# e3_tp2_ej4.net
KiCad netlist of a schematic drawn in Altium Designer
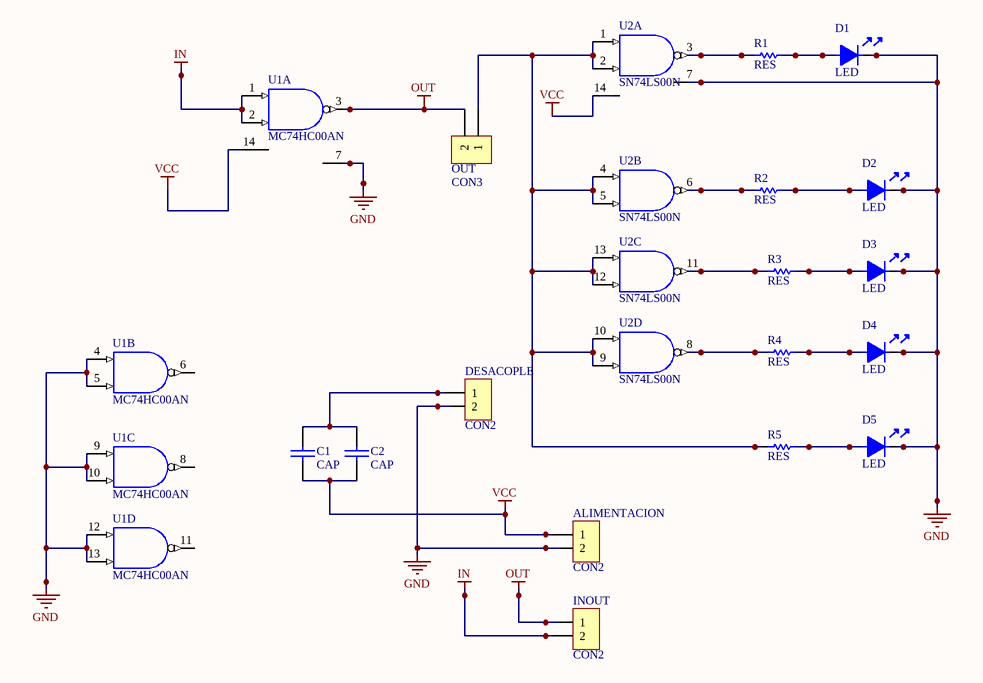
[diagram p0: e3_tp2_ej4.SchDoc]

(export (version "E")
  (design (tool "Eeschema 10.0.6"))
  (components
    (comp (ref "ALIMENTACION") (value "CON2") (footprint "SIP2") (libsource (lib "LIBEBAL") (part "CON2")))
    (comp (ref "C1") (value "CAP") (footprint "CAP200") (libsource (lib "LIBEBAL") (part "CAP")))
    (comp (ref "C2") (value "CAP") (footprint "CAP200") (libsource (lib "LIBEBAL") (part "CAP")))
    (comp (ref "D1") (value "LED") (footprint "LED3") (libsource (lib "LIBEBAL") (part "LED")))
    (comp (ref "D2") (value "LED") (footprint "LED3") (libsource (lib "LIBEBAL") (part "LED")))
    (comp (ref "D3") (value "LED") (footprint "LED3") (libsource (lib "LIBEBAL") (part "LED")))
    (comp (ref "D4") (value "LED") (footprint "LED3") (libsource (lib "LIBEBAL") (part "LED")))
    (comp (ref "D5") (value "LED") (footprint "LED3") (libsource (lib "LIBEBAL") (part "LED")))
    (comp (ref "DESACOPLE") (value "CON2") (footprint "SIP2") (libsource (lib "LIBEBAL") (part "CON2")))
    (comp (ref "INOUT") (value "CON2") (footprint "SIP2") (libsource (lib "LIBEBAL") (part "CON2")))
    (comp (ref "OUT") (value "CON3") (footprint "SIP2") (libsource (lib "") (part "CON2_1")))
    (comp (ref "R1") (value "RES") (footprint "RES300") (libsource (lib "LIBEBAL") (part "RES")))
    (comp (ref "R2") (value "RES") (footprint "RES300") (libsource (lib "LIBEBAL") (part "RES")))
    (comp (ref "R3") (value "RES") (footprint "RES300") (libsource (lib "LIBEBAL") (part "RES")))
    (comp (ref "R4") (value "RES") (footprint "RES300") (libsource (lib "LIBEBAL") (part "RES")))
    (comp (ref "R5") (value "RES") (footprint "RES300") (libsource (lib "LIBEBAL") (part "RES")))
    (comp (ref "U1")
      (value "MC74HC00AN")
      (footprint "646-06")
      (description "Quad 2-Input NAND Gate")
      (fields (field (name "PUBLISHER") "Altium Limited"))
      (libsource (lib "ON Semi Logic Gate") (part "MC74HC00AN"))
    )
    (comp (ref "U2")
      (value "SN74LS00N")
      (footprint "646-06")
      (description "Quad 2-Input NAND Gate")
      (fields (field (name "PUBLISHER") "Altium Limited"))
      (libsource (lib "ON Semi Logic Gate") (part "SN74LS00N"))
    )
  )
  (nets
    (net (code "1") (name "GND") (class "Default")
      (node (ref "ALIMENTACION") (pin "2") (pinfunction "2_2") (pintype "passive"))
      (node (ref "D1") (pin "2") (pinfunction "2_2") (pintype "passive"))
      (node (ref "D2") (pin "2") (pinfunction "2_2") (pintype "passive"))
      (node (ref "D3") (pin "2") (pinfunction "2_2") (pintype "passive"))
      (node (ref "D4") (pin "2") (pinfunction "2_2") (pintype "passive"))
      (node (ref "D5") (pin "2") (pinfunction "2_2") (pintype "passive"))
      (node (ref "DESACOPLE") (pin "2") (pinfunction "2_2") (pintype "passive"))
      (node (ref "U1") (pin "10") (pinfunction "B_10") (pintype "input"))
      (node (ref "U1") (pin "12") (pinfunction "A_12") (pintype "input"))
      (node (ref "U1") (pin "13") (pinfunction "B_13") (pintype "input"))
      (node (ref "U1") (pin "4") (pinfunction "A_4") (pintype "input"))
      (node (ref "U1") (pin "5") (pinfunction "B_5") (pintype "input"))
      (node (ref "U1") (pin "7") (pinfunction "GND_7") (pintype "power_in"))
      (node (ref "U1") (pin "9") (pinfunction "A_9") (pintype "input"))
      (node (ref "U2") (pin "7") (pinfunction "GND_7") (pintype "power_in"))
    )
    (net (code "2") (name "IN") (class "Default")
      (node (ref "INOUT") (pin "2") (pinfunction "2_2") (pintype "passive"))
      (node (ref "U1") (pin "1") (pinfunction "A_1") (pintype "input"))
      (node (ref "U1") (pin "2") (pinfunction "B_2") (pintype "input"))
    )
    (net (code "3") (name "Net-(C1-Pad1)") (class "Default")
      (node (ref "C1") (pin "1") (pinfunction "1_1") (pintype "passive"))
      (node (ref "C2") (pin "1") (pinfunction "1_1") (pintype "passive"))
      (node (ref "DESACOPLE") (pin "1") (pinfunction "1_1") (pintype "passive"))
    )
    (net (code "4") (name "Net-(D1-Pad1)") (class "Default")
      (node (ref "D1") (pin "1") (pinfunction "1_1") (pintype "passive"))
      (node (ref "R1") (pin "2") (pinfunction "2_2") (pintype "passive"))
    )
    (net (code "5") (name "Net-(D2-Pad1)") (class "Default")
      (node (ref "D2") (pin "1") (pinfunction "1_1") (pintype "passive"))
      (node (ref "R2") (pin "2") (pinfunction "2_2") (pintype "passive"))
    )
    (net (code "6") (name "Net-(D3-Pad1)") (class "Default")
      (node (ref "D3") (pin "1") (pinfunction "1_1") (pintype "passive"))
      (node (ref "R3") (pin "2") (pinfunction "2_2") (pintype "passive"))
    )
    (net (code "7") (name "Net-(D4-Pad1)") (class "Default")
      (node (ref "D4") (pin "1") (pinfunction "1_1") (pintype "passive"))
      (node (ref "R4") (pin "2") (pinfunction "2_2") (pintype "passive"))
    )
    (net (code "8") (name "Net-(D5-Pad1)") (class "Default")
      (node (ref "D5") (pin "1") (pinfunction "1_1") (pintype "passive"))
      (node (ref "R5") (pin "2") (pinfunction "2_2") (pintype "passive"))
    )
    (net (code "9") (name "Net-(U2A-A)") (class "Default")
      (node (ref "OUT") (pin "1") (pinfunction "1_1") (pintype "passive"))
      (node (ref "R5") (pin "1") (pinfunction "1_1") (pintype "passive"))
      (node (ref "U2") (pin "1") (pinfunction "A_1") (pintype "input"))
      (node (ref "U2") (pin "10") (pinfunction "A_10") (pintype "input"))
      (node (ref "U2") (pin "12") (pinfunction "B_12") (pintype "input"))
      (node (ref "U2") (pin "13") (pinfunction "A_13") (pintype "input"))
      (node (ref "U2") (pin "2") (pinfunction "B_2") (pintype "input"))
      (node (ref "U2") (pin "4") (pinfunction "A_4") (pintype "input"))
      (node (ref "U2") (pin "5") (pinfunction "B_5") (pintype "input"))
      (node (ref "U2") (pin "9") (pinfunction "B_9") (pintype "input"))
    )
    (net (code "10") (name "Net-(U2A-~{O})") (class "Default")
      (node (ref "R1") (pin "1") (pinfunction "1_1") (pintype "passive"))
      (node (ref "U2") (pin "3") (pinfunction "~{O}_3") (pintype "output"))
    )
    (net (code "11") (name "Net-(U2B-~{O})") (class "Default")
      (node (ref "R2") (pin "1") (pinfunction "1_1") (pintype "passive"))
      (node (ref "U2") (pin "6") (pinfunction "~{O}_6") (pintype "output"))
    )
    (net (code "12") (name "Net-(U2C-~{O})") (class "Default")
      (node (ref "R3") (pin "1") (pinfunction "1_1") (pintype "passive"))
      (node (ref "U2") (pin "11") (pinfunction "~{O}_11") (pintype "output"))
    )
    (net (code "13") (name "Net-(U2D-~{O})") (class "Default")
      (node (ref "R4") (pin "1") (pinfunction "1_1") (pintype "passive"))
      (node (ref "U2") (pin "8") (pinfunction "~{O}_8") (pintype "output"))
    )
    (net (code "14") (name "OUT") (class "Default")
      (node (ref "INOUT") (pin "1") (pinfunction "1_1") (pintype "passive"))
      (node (ref "OUT") (pin "2") (pinfunction "2_2") (pintype "passive"))
      (node (ref "U1") (pin "3") (pinfunction "~{Y}_3") (pintype "output"))
    )
    (net (code "15") (name "VCC") (class "Default")
      (node (ref "ALIMENTACION") (pin "1") (pinfunction "1_1") (pintype "passive"))
      (node (ref "C1") (pin "2") (pinfunction "2_2") (pintype "passive"))
      (node (ref "C2") (pin "2") (pinfunction "2_2") (pintype "passive"))
      (node (ref "U1") (pin "14") (pinfunction "VCC_14") (pintype "power_in"))
      (node (ref "U2") (pin "14") (pinfunction "VCC_14") (pintype "power_in"))
    )
    (net (code "16") (name "unconnected-(U1B-~{Y}-Pad6)") (class "Default")
      (node (ref "U1") (pin "6") (pinfunction "~{Y}_6") (pintype "output"))
    )
    (net (code "17") (name "unconnected-(U1C-~{Y}-Pad8)") (class "Default")
      (node (ref "U1") (pin "8") (pinfunction "~{Y}_8") (pintype "output"))
    )
    (net (code "18") (name "unconnected-(U1D-~{Y}-Pad11)") (class "Default")
      (node (ref "U1") (pin "11") (pinfunction "~{Y}_11") (pintype "output"))
    )
  )
)
